# CANOPi_Topboard_USB3.net
KiCad netlist of a schematic drawn in Altium Designer
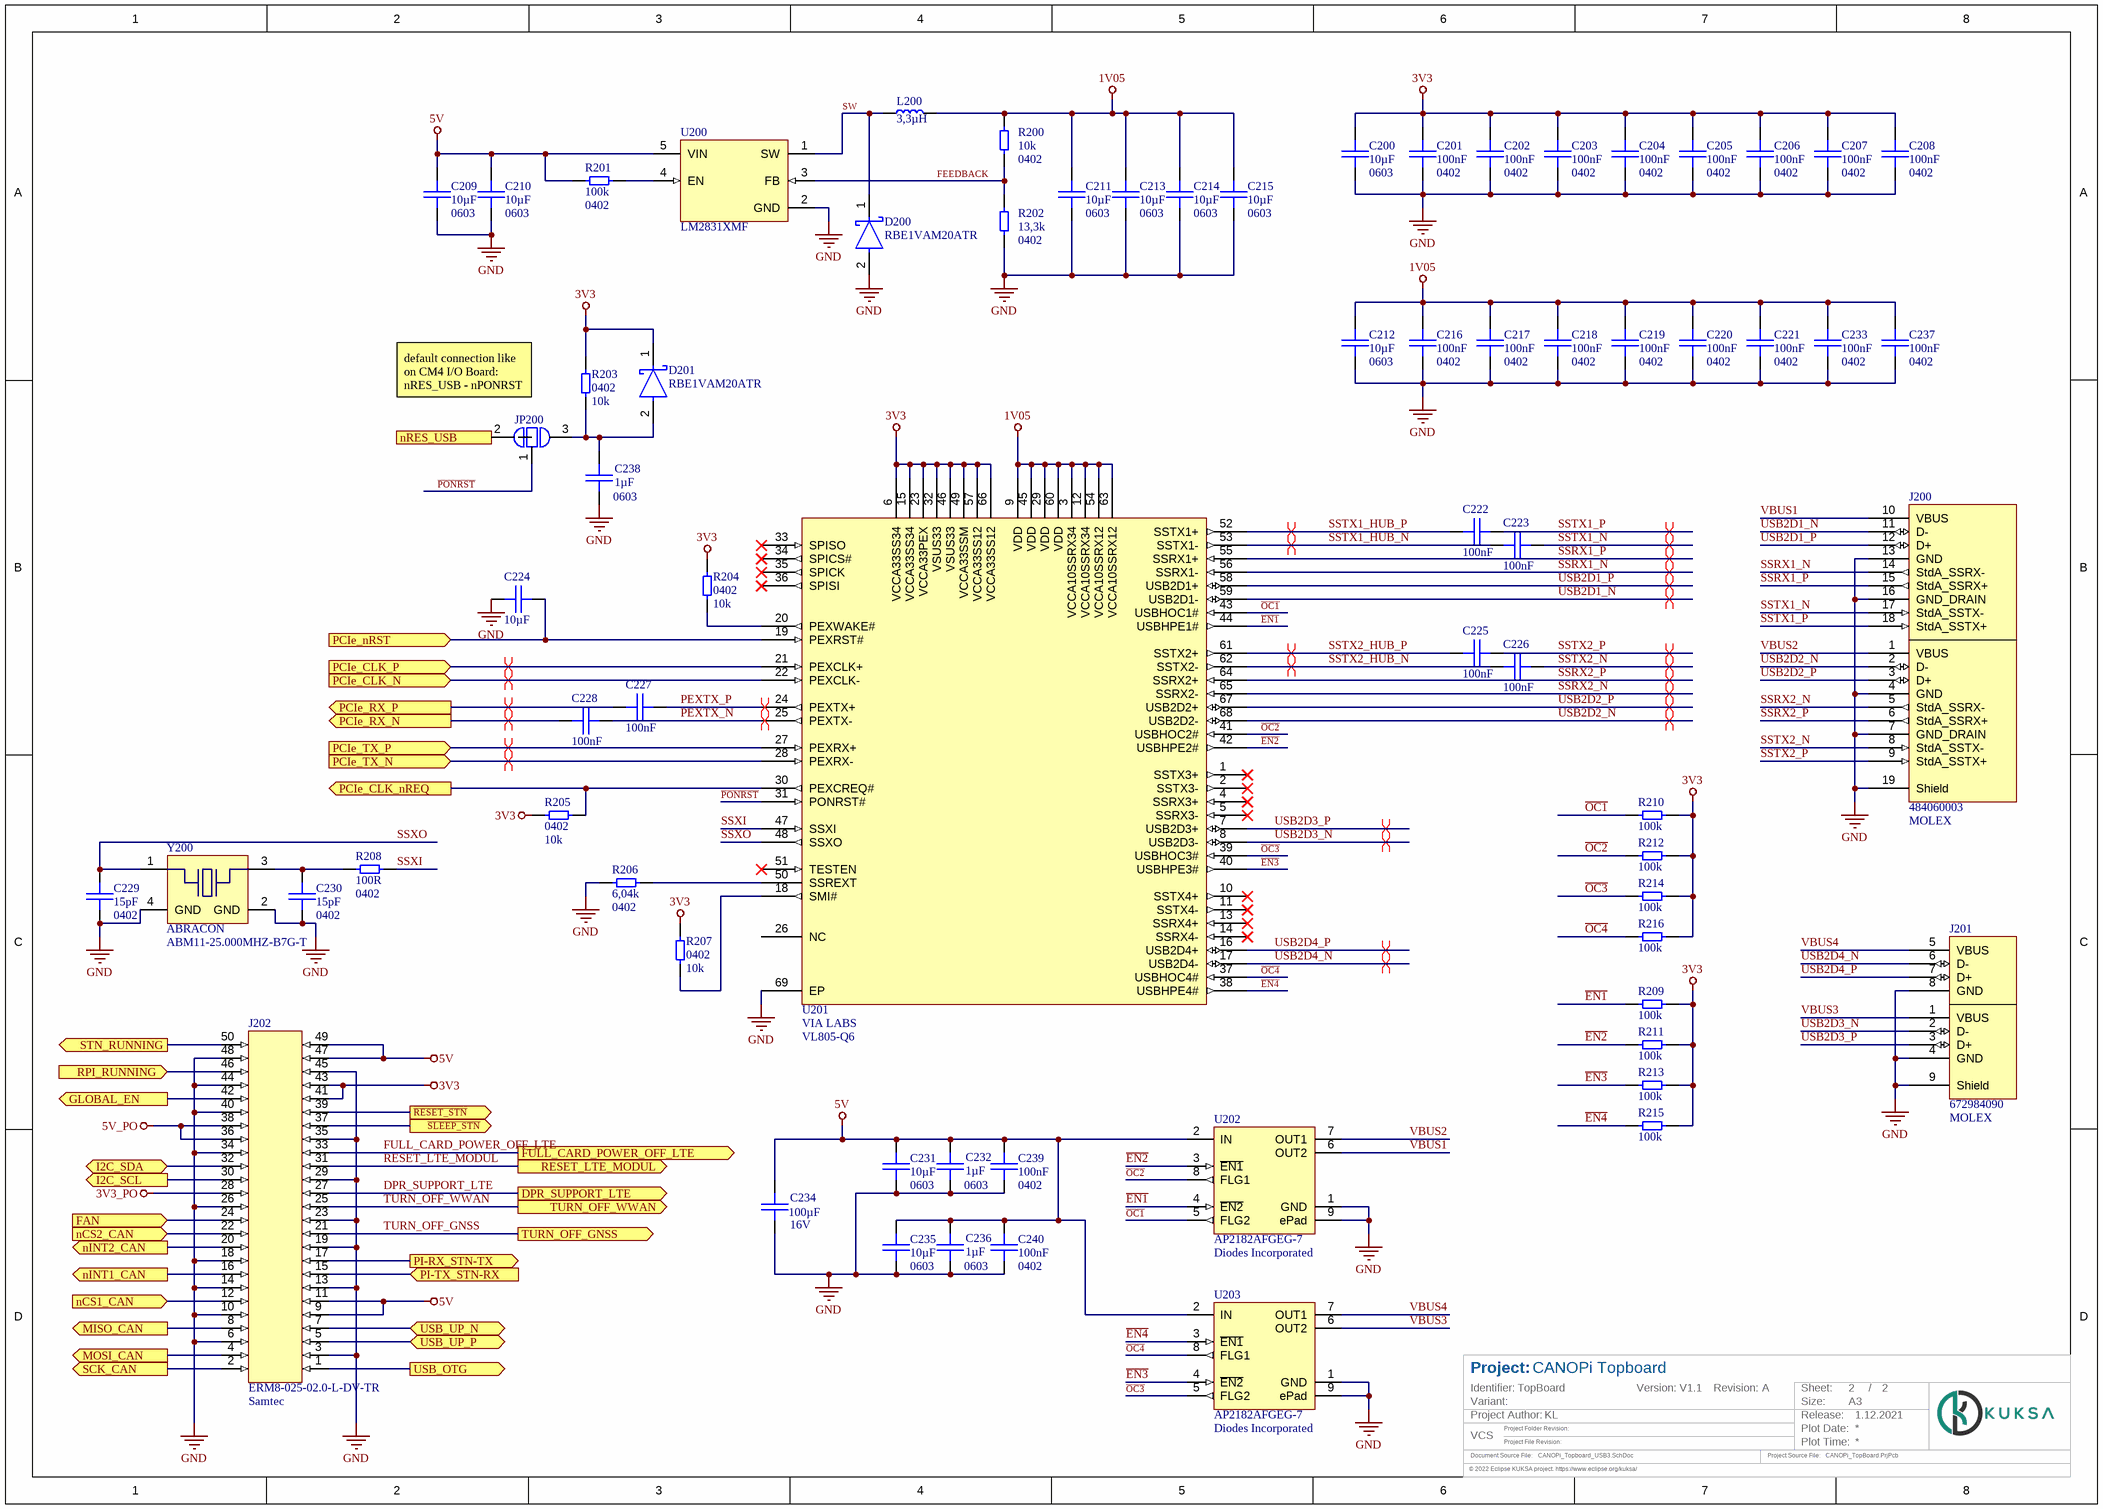
[diagram p0: CANOPi_Topboard_USB3.SchDoc]

(export (version "E")
  (design (tool "Eeschema 10.0.6"))
  (components
    (comp (ref "C200")
      (value "CAP 0603 10µF -20% +20% 6.3V X5R")
      (footprint "CAP 0603 [1608 Metric] X080 N")
      (description "SMT 10µF ±20% 6,3 V Keramikkondensatoren X5R")
      (fields
        (field (name "MANUFACTURER PART NUMBER") "GRM188R60J106ME84")
        (field (name "CAPACITANCE") "10µF")
        (field (name "MANUFACTURER") "MURATA")
        (field (name "CASE") "0603")
      )
      (libsource (lib "ShareLib") (part "Capacitor non-polarized - Standard Schematic"))
    )
    (comp (ref "C201")
      (value "CAP 0402 100n -10% +10% 6.3V X7R")
      (footprint "CAP 0402 [1005 Metric] X050 N")
      (description "SMD/SMT 0402 6.3V -10% +10% X7R - Multilayer Ceramic Capacitors MLCC")
      (fields
        (field (name "MANUFACTURER") "MURATA")
        (field (name "CAPACITANCE") "100nF")
        (field (name "MANUFACTURER PART NUMBER") "GRM155R70J104KA01#")
        (field (name "CASE") "0402")
      )
      (libsource (lib "ShareLib") (part "Capacitor non-polarized - Standard Schematic"))
    )
    (comp (ref "C202")
      (value "CAP 0402 100n -10% +10% 6.3V X7R")
      (footprint "CAP 0402 [1005 Metric] X050 N")
      (description "SMD/SMT 0402 6.3V -10% +10% X7R - Multilayer Ceramic Capacitors MLCC")
      (fields
        (field (name "MANUFACTURER") "MURATA")
        (field (name "CAPACITANCE") "100nF")
        (field (name "MANUFACTURER PART NUMBER") "GRM155R70J104KA01#")
        (field (name "CASE") "0402")
      )
      (libsource (lib "ShareLib") (part "Capacitor non-polarized - Standard Schematic"))
    )
    (comp (ref "C203")
      (value "CAP 0402 100n -10% +10% 6.3V X7R")
      (footprint "CAP 0402 [1005 Metric] X050 N")
      (description "SMD/SMT 0402 6.3V -10% +10% X7R - Multilayer Ceramic Capacitors MLCC")
      (fields
        (field (name "MANUFACTURER") "MURATA")
        (field (name "CAPACITANCE") "100nF")
        (field (name "MANUFACTURER PART NUMBER") "GRM155R70J104KA01#")
        (field (name "CASE") "0402")
      )
      (libsource (lib "ShareLib") (part "Capacitor non-polarized - Standard Schematic"))
    )
    (comp (ref "C204")
      (value "CAP 0402 100n -10% +10% 6.3V X7R")
      (footprint "CAP 0402 [1005 Metric] X050 N")
      (description "SMD/SMT 0402 6.3V -10% +10% X7R - Multilayer Ceramic Capacitors MLCC")
      (fields
        (field (name "MANUFACTURER") "MURATA")
        (field (name "CAPACITANCE") "100nF")
        (field (name "MANUFACTURER PART NUMBER") "GRM155R70J104KA01#")
        (field (name "CASE") "0402")
      )
      (libsource (lib "ShareLib") (part "Capacitor non-polarized - Standard Schematic"))
    )
    (comp (ref "C205")
      (value "CAP 0402 100n -10% +10% 6.3V X7R")
      (footprint "CAP 0402 [1005 Metric] X050 N")
      (description "SMD/SMT 0402 6.3V -10% +10% X7R - Multilayer Ceramic Capacitors MLCC")
      (fields
        (field (name "MANUFACTURER") "MURATA")
        (field (name "CAPACITANCE") "100nF")
        (field (name "MANUFACTURER PART NUMBER") "GRM155R70J104KA01#")
        (field (name "CASE") "0402")
      )
      (libsource (lib "ShareLib") (part "Capacitor non-polarized - Standard Schematic"))
    )
    (comp (ref "C206")
      (value "CAP 0402 100n -10% +10% 6.3V X7R")
      (footprint "CAP 0402 [1005 Metric] X050 N")
      (description "SMD/SMT 0402 6.3V -10% +10% X7R - Multilayer Ceramic Capacitors MLCC")
      (fields
        (field (name "MANUFACTURER") "MURATA")
        (field (name "CAPACITANCE") "100nF")
        (field (name "MANUFACTURER PART NUMBER") "GRM155R70J104KA01#")
        (field (name "CASE") "0402")
      )
      (libsource (lib "ShareLib") (part "Capacitor non-polarized - Standard Schematic"))
    )
    (comp (ref "C207")
      (value "CAP 0402 100n -10% +10% 6.3V X7R")
      (footprint "CAP 0402 [1005 Metric] X050 N")
      (description "SMD/SMT 0402 6.3V -10% +10% X7R - Multilayer Ceramic Capacitors MLCC")
      (fields
        (field (name "MANUFACTURER") "MURATA")
        (field (name "CAPACITANCE") "100nF")
        (field (name "MANUFACTURER PART NUMBER") "GRM155R70J104KA01#")
        (field (name "CASE") "0402")
      )
      (libsource (lib "ShareLib") (part "Capacitor non-polarized - Standard Schematic"))
    )
    (comp (ref "C208")
      (value "CAP 0402 100n -10% +10% 6.3V X7R")
      (footprint "CAP 0402 [1005 Metric] X050 N")
      (description "SMD/SMT 0402 6.3V -10% +10% X7R - Multilayer Ceramic Capacitors MLCC")
      (fields
        (field (name "MANUFACTURER") "MURATA")
        (field (name "CAPACITANCE") "100nF")
        (field (name "MANUFACTURER PART NUMBER") "GRM155R70J104KA01#")
        (field (name "CASE") "0402")
      )
      (libsource (lib "ShareLib") (part "Capacitor non-polarized - Standard Schematic"))
    )
    (comp (ref "C209")
      (value "CAP 0603 10µF -20% +20% 6.3V X5R")
      (footprint "CAP 0603 [1608 Metric] X080 N")
      (description "SMT 10µF ±20% 6,3 V Keramikkondensatoren X5R")
      (fields
        (field (name "MANUFACTURER PART NUMBER") "GRM188R60J106ME84")
        (field (name "CAPACITANCE") "10µF")
        (field (name "MANUFACTURER") "MURATA")
        (field (name "CASE") "0603")
      )
      (libsource (lib "ShareLib") (part "Capacitor non-polarized - Standard Schematic"))
    )
    (comp (ref "C210")
      (value "CAP 0603 10µF -20% +20% 6.3V X5R")
      (footprint "CAP 0603 [1608 Metric] X080 N")
      (description "SMT 10µF ±20% 6,3 V Keramikkondensatoren X5R")
      (fields
        (field (name "MANUFACTURER PART NUMBER") "GRM188R60J106ME84")
        (field (name "CAPACITANCE") "10µF")
        (field (name "MANUFACTURER") "MURATA")
        (field (name "CASE") "0603")
      )
      (libsource (lib "ShareLib") (part "Capacitor non-polarized - Standard Schematic"))
    )
    (comp (ref "C211")
      (value "CAP 0603 10µF -20% +20% 6.3V X5R")
      (footprint "CAP 0603 [1608 Metric] X080 N")
      (description "SMT 10µF ±20% 6,3 V Keramikkondensatoren X5R")
      (fields
        (field (name "MANUFACTURER PART NUMBER") "GRM188R60J106ME84")
        (field (name "CAPACITANCE") "10µF")
        (field (name "MANUFACTURER") "MURATA")
        (field (name "CASE") "0603")
      )
      (libsource (lib "ShareLib") (part "Capacitor non-polarized - Standard Schematic"))
    )
    (comp (ref "C212")
      (value "CAP 0603 10µF -20% +20% 6.3V X5R")
      (footprint "CAP 0603 [1608 Metric] X080 N")
      (description "SMT 10µF ±20% 6,3 V Keramikkondensatoren X5R")
      (fields
        (field (name "MANUFACTURER PART NUMBER") "GRM188R60J106ME84")
        (field (name "CAPACITANCE") "10µF")
        (field (name "MANUFACTURER") "MURATA")
        (field (name "CASE") "0603")
      )
      (libsource (lib "ShareLib") (part "Capacitor non-polarized - Standard Schematic"))
    )
    (comp (ref "C213")
      (value "CAP 0603 10µF -20% +20% 6.3V X5R")
      (footprint "CAP 0603 [1608 Metric] X080 N")
      (description "SMT 10µF ±20% 6,3 V Keramikkondensatoren X5R")
      (fields
        (field (name "MANUFACTURER PART NUMBER") "GRM188R60J106ME84")
        (field (name "CAPACITANCE") "10µF")
        (field (name "MANUFACTURER") "MURATA")
        (field (name "CASE") "0603")
      )
      (libsource (lib "ShareLib") (part "Capacitor non-polarized - Standard Schematic"))
    )
    (comp (ref "C214")
      (value "CAP 0603 10µF -20% +20% 6.3V X5R")
      (footprint "CAP 0603 [1608 Metric] X080 N")
      (description "SMT 10µF ±20% 6,3 V Keramikkondensatoren X5R")
      (fields
        (field (name "MANUFACTURER PART NUMBER") "GRM188R60J106ME84")
        (field (name "CAPACITANCE") "10µF")
        (field (name "MANUFACTURER") "MURATA")
        (field (name "CASE") "0603")
      )
      (libsource (lib "ShareLib") (part "Capacitor non-polarized - Standard Schematic"))
    )
    (comp (ref "C215")
      (value "CAP 0603 10µF -20% +20% 6.3V X5R")
      (footprint "CAP 0603 [1608 Metric] X080 N")
      (description "SMT 10µF ±20% 6,3 V Keramikkondensatoren X5R")
      (fields
        (field (name "MANUFACTURER PART NUMBER") "GRM188R60J106ME84")
        (field (name "CAPACITANCE") "10µF")
        (field (name "MANUFACTURER") "MURATA")
        (field (name "CASE") "0603")
      )
      (libsource (lib "ShareLib") (part "Capacitor non-polarized - Standard Schematic"))
    )
    (comp (ref "C216")
      (value "CAP 0402 100n -10% +10% 6.3V X7R")
      (footprint "CAP 0402 [1005 Metric] X050 N")
      (description "SMD/SMT 0402 6.3V -10% +10% X7R - Multilayer Ceramic Capacitors MLCC")
      (fields
        (field (name "MANUFACTURER") "MURATA")
        (field (name "CAPACITANCE") "100nF")
        (field (name "MANUFACTURER PART NUMBER") "GRM155R70J104KA01#")
        (field (name "CASE") "0402")
      )
      (libsource (lib "ShareLib") (part "Capacitor non-polarized - Standard Schematic"))
    )
    (comp (ref "C217")
      (value "CAP 0402 100n -10% +10% 6.3V X7R")
      (footprint "CAP 0402 [1005 Metric] X050 N")
      (description "SMD/SMT 0402 6.3V -10% +10% X7R - Multilayer Ceramic Capacitors MLCC")
      (fields
        (field (name "MANUFACTURER") "MURATA")
        (field (name "CAPACITANCE") "100nF")
        (field (name "MANUFACTURER PART NUMBER") "GRM155R70J104KA01#")
        (field (name "CASE") "0402")
      )
      (libsource (lib "ShareLib") (part "Capacitor non-polarized - Standard Schematic"))
    )
    (comp (ref "C218")
      (value "CAP 0402 100n -10% +10% 6.3V X7R")
      (footprint "CAP 0402 [1005 Metric] X050 N")
      (description "SMD/SMT 0402 6.3V -10% +10% X7R - Multilayer Ceramic Capacitors MLCC")
      (fields
        (field (name "MANUFACTURER") "MURATA")
        (field (name "CAPACITANCE") "100nF")
        (field (name "MANUFACTURER PART NUMBER") "GRM155R70J104KA01#")
        (field (name "CASE") "0402")
      )
      (libsource (lib "ShareLib") (part "Capacitor non-polarized - Standard Schematic"))
    )
    (comp (ref "C219")
      (value "CAP 0402 100n -10% +10% 6.3V X7R")
      (footprint "CAP 0402 [1005 Metric] X050 N")
      (description "SMD/SMT 0402 6.3V -10% +10% X7R - Multilayer Ceramic Capacitors MLCC")
      (fields
        (field (name "MANUFACTURER") "MURATA")
        (field (name "CAPACITANCE") "100nF")
        (field (name "MANUFACTURER PART NUMBER") "GRM155R70J104KA01#")
        (field (name "CASE") "0402")
      )
      (libsource (lib "ShareLib") (part "Capacitor non-polarized - Standard Schematic"))
    )
    (comp (ref "C220")
      (value "CAP 0402 100n -10% +10% 6.3V X7R")
      (footprint "CAP 0402 [1005 Metric] X050 N")
      (description "SMD/SMT 0402 6.3V -10% +10% X7R - Multilayer Ceramic Capacitors MLCC")
      (fields
        (field (name "MANUFACTURER") "MURATA")
        (field (name "CAPACITANCE") "100nF")
        (field (name "MANUFACTURER PART NUMBER") "GRM155R70J104KA01#")
        (field (name "CASE") "0402")
      )
      (libsource (lib "ShareLib") (part "Capacitor non-polarized - Standard Schematic"))
    )
    (comp (ref "C221")
      (value "CAP 0402 100n -10% +10% 6.3V X7R")
      (footprint "CAP 0402 [1005 Metric] X050 N")
      (description "SMD/SMT 0402 6.3V -10% +10% X7R - Multilayer Ceramic Capacitors MLCC")
      (fields
        (field (name "MANUFACTURER") "MURATA")
        (field (name "CAPACITANCE") "100nF")
        (field (name "MANUFACTURER PART NUMBER") "GRM155R70J104KA01#")
        (field (name "CASE") "0402")
      )
      (libsource (lib "ShareLib") (part "Capacitor non-polarized - Standard Schematic"))
    )
    (comp (ref "C222")
      (value "CAP 0402 100n -10% +10% 6.3V X7R")
      (footprint "CAP 0402 [1005 Metric] X050 N")
      (description "SMD/SMT 0402 6.3V -10% +10% X7R - Multilayer Ceramic Capacitors MLCC")
      (fields
        (field (name "MANUFACTURER") "MURATA")
        (field (name "CAPACITANCE") "100nF")
        (field (name "MANUFACTURER PART NUMBER") "GRM155R70J104KA01#")
      )
      (libsource (lib "ShareLib") (part "Capacitor non-polarized - Standard Schematic"))
    )
    (comp (ref "C223")
      (value "CAP 0402 100n -10% +10% 6.3V X7R")
      (footprint "CAP 0402 [1005 Metric] X050 N")
      (description "SMD/SMT 0402 6.3V -10% +10% X7R - Multilayer Ceramic Capacitors MLCC")
      (fields
        (field (name "MANUFACTURER") "MURATA")
        (field (name "CAPACITANCE") "100nF")
        (field (name "MANUFACTURER PART NUMBER") "GRM155R70J104KA01#")
      )
      (libsource (lib "ShareLib") (part "Capacitor non-polarized - Standard Schematic"))
    )
    (comp (ref "C224")
      (value "CAP 0603 10µF -20% +20% 6.3V X5R")
      (footprint "CAP 0603 [1608 Metric] X080 N")
      (description "SMT 10µF ±20% 6,3 V Keramikkondensatoren X5R")
      (fields
        (field (name "MANUFACTURER PART NUMBER") "GRM188R60J106ME84")
        (field (name "CAPACITANCE") "10µF")
        (field (name "MANUFACTURER") "MURATA")
      )
      (libsource (lib "ShareLib") (part "Capacitor non-polarized - Standard Schematic"))
    )
    (comp (ref "C225")
      (value "CAP 0402 100n -10% +10% 6.3V X7R")
      (footprint "CAP 0402 [1005 Metric] X050 N")
      (description "SMD/SMT 0402 6.3V -10% +10% X7R - Multilayer Ceramic Capacitors MLCC")
      (fields
        (field (name "MANUFACTURER") "MURATA")
        (field (name "CAPACITANCE") "100nF")
        (field (name "MANUFACTURER PART NUMBER") "GRM155R70J104KA01#")
      )
      (libsource (lib "ShareLib") (part "Capacitor non-polarized - Standard Schematic"))
    )
    (comp (ref "C226")
      (value "CAP 0402 100n -10% +10% 6.3V X7R")
      (footprint "CAP 0402 [1005 Metric] X050 N")
      (description "SMD/SMT 0402 6.3V -10% +10% X7R - Multilayer Ceramic Capacitors MLCC")
      (fields
        (field (name "MANUFACTURER") "MURATA")
        (field (name "CAPACITANCE") "100nF")
        (field (name "MANUFACTURER PART NUMBER") "GRM155R70J104KA01#")
      )
      (libsource (lib "ShareLib") (part "Capacitor non-polarized - Standard Schematic"))
    )
    (comp (ref "C227")
      (value "CAP 0402 100n -10% +10% 6.3V X7R")
      (footprint "CAP 0402 [1005 Metric] X050 N")
      (description "SMD/SMT 0402 6.3V -10% +10% X7R - Multilayer Ceramic Capacitors MLCC")
      (fields
        (field (name "MANUFACTURER") "MURATA")
        (field (name "CAPACITANCE") "100nF")
        (field (name "MANUFACTURER PART NUMBER") "GRM155R70J104KA01#")
      )
      (libsource (lib "ShareLib") (part "Capacitor non-polarized - Standard Schematic"))
    )
    (comp (ref "C228")
      (value "CAP 0402 100n -10% +10% 6.3V X7R")
      (footprint "CAP 0402 [1005 Metric] X050 N")
      (description "SMD/SMT 0402 6.3V -10% +10% X7R - Multilayer Ceramic Capacitors MLCC")
      (fields
        (field (name "MANUFACTURER") "MURATA")
        (field (name "CAPACITANCE") "100nF")
        (field (name "MANUFACTURER PART NUMBER") "GRM155R70J104KA01#")
      )
      (libsource (lib "ShareLib") (part "Capacitor non-polarized - Standard Schematic"))
    )
    (comp (ref "C229")
      (value "CAP 0402 15p -2% +2% 25V C0G")
      (footprint "CAP 0402 [1005 Metric] X050 N")
      (description "SMD/SMT 0402 25V -2% +2% C0G - Multilayer Ceramic Capacitors MLCC")
      (fields
        (field (name "MANUFACTURER") "MURATA")
        (field (name "MANUFACTURER PART NUMBER") "GRM1555C1E150GA01#")
        (field (name "CASE") "0402")
        (field (name "CAPACITANCE") "15pF")
      )
      (libsource (lib "ShareLib") (part "Capacitor non-polarized - Standard Schematic"))
    )
    (comp (ref "C230")
      (value "CAP 0402 15p -2% +2% 25V C0G")
      (footprint "CAP 0402 [1005 Metric] X050 N")
      (description "SMD/SMT 0402 25V -2% +2% C0G - Multilayer Ceramic Capacitors MLCC")
      (fields
        (field (name "MANUFACTURER") "MURATA")
        (field (name "MANUFACTURER PART NUMBER") "GRM1555C1E150GA01#")
        (field (name "CASE") "0402")
        (field (name "CAPACITANCE") "15pF")
      )
      (libsource (lib "ShareLib") (part "Capacitor non-polarized - Standard Schematic"))
    )
    (comp (ref "C231")
      (value "CAP 0603 10µF -20% +20% 6.3V X5R")
      (footprint "CAP 0603 [1608 Metric] X080 N")
      (description "SMT 10µF ±20% 6,3 V Keramikkondensatoren X5R")
      (fields
        (field (name "MANUFACTURER PART NUMBER") "GRM188R60J106ME84")
        (field (name "CAPACITANCE") "10µF")
        (field (name "MANUFACTURER") "MURATA")
        (field (name "CASE") "0603")
      )
      (libsource (lib "ShareLib") (part "Capacitor non-polarized - Standard Schematic"))
    )
    (comp (ref "C232")
      (value "CAP 0603 1u -10% +10% 10V X7R")
      (footprint "CAP 0603 [1608 Metric] X080 N")
      (description "SMD/SMT 0603 10V -10% +10% X7R - Multilayer Ceramic Capacitors MLCC")
      (fields
        (field (name "CAPACITANCE") "1µF")
        (field (name "MANUFACTURER PART NUMBER") "GRM188R71A105KA61#")
        (field (name "MANUFACTURER") "MURATA")
        (field (name "CASE") "0603")
      )
      (libsource (lib "ShareLib") (part "Capacitor non-polarized - Standard Schematic"))
    )
    (comp (ref "C233")
      (value "CAP 0402 100n -10% +10% 6.3V X7R")
      (footprint "CAP 0402 [1005 Metric] X050 N")
      (description "SMD/SMT 0402 6.3V -10% +10% X7R - Multilayer Ceramic Capacitors MLCC")
      (fields
        (field (name "MANUFACTURER") "MURATA")
        (field (name "CAPACITANCE") "100nF")
        (field (name "MANUFACTURER PART NUMBER") "GRM155R70J104KA01#")
        (field (name "CASE") "0402")
      )
      (libsource (lib "ShareLib") (part "Capacitor non-polarized - Standard Schematic"))
    )
    (comp (ref "C234")
      (value "CAP 1210 100µF +/-20% 16V X5R")
      (footprint "CAP 1210 [3225 Metric] X250 N")
      (description "100µF ±20% 16V Ceramic Capacitor X5R 1210 (3225 Metric)")
      (fields
        (field (name "MANUFACTURER PART NUMBER") "EMK325ABJ107MM-T")
        (field (name "VOLTAGE RATING") "16V")
        (field (name "MANUFACTURER") "TAIYO YUDEN")
        (field (name "CAPACITANCE") "100µF")
      )
      (libsource (lib "ShareLib") (part "Capacitor non-polarized - Standard Schematic"))
    )
    (comp (ref "C235")
      (value "CAP 0603 10µF -20% +20% 6.3V X5R")
      (footprint "CAP 0603 [1608 Metric] X080 N")
      (description "SMT 10µF ±20% 6,3 V Keramikkondensatoren X5R")
      (fields
        (field (name "MANUFACTURER PART NUMBER") "GRM188R60J106ME84")
        (field (name "CAPACITANCE") "10µF")
        (field (name "MANUFACTURER") "MURATA")
        (field (name "CASE") "0603")
      )
      (libsource (lib "ShareLib") (part "Capacitor non-polarized - Standard Schematic"))
    )
    (comp (ref "C236")
      (value "CAP 0603 1u -10% +10% 10V X7R")
      (footprint "CAP 0603 [1608 Metric] X080 N")
      (description "SMD/SMT 0603 10V -10% +10% X7R - Multilayer Ceramic Capacitors MLCC")
      (fields
        (field (name "CAPACITANCE") "1µF")
        (field (name "MANUFACTURER PART NUMBER") "GRM188R71A105KA61#")
        (field (name "MANUFACTURER") "MURATA")
        (field (name "CASE") "0603")
      )
      (libsource (lib "ShareLib") (part "Capacitor non-polarized - Standard Schematic"))
    )
    (comp (ref "C237")
      (value "CAP 0402 100n -10% +10% 6.3V X7R")
      (footprint "CAP 0402 [1005 Metric] X050 N")
      (description "SMD/SMT 0402 6.3V -10% +10% X7R - Multilayer Ceramic Capacitors MLCC")
      (fields
        (field (name "MANUFACTURER") "MURATA")
        (field (name "CAPACITANCE") "100nF")
        (field (name "MANUFACTURER PART NUMBER") "GRM155R70J104KA01#")
        (field (name "CASE") "0402")
      )
      (libsource (lib "ShareLib") (part "Capacitor non-polarized - Standard Schematic"))
    )
    (comp (ref "C238")
      (value "CAP 0603 1u -10% +10% 10V X7R")
      (footprint "CAP 0603 [1608 Metric] X080 N")
      (description "SMD/SMT 0603 10V -10% +10% X7R - Multilayer Ceramic Capacitors MLCC")
      (fields
        (field (name "CAPACITANCE") "1µF")
        (field (name "MANUFACTURER PART NUMBER") "GRM188R71A105KA61#")
        (field (name "MANUFACTURER") "MURATA")
        (field (name "CASE") "0603")
      )
      (libsource (lib "ShareLib") (part "Capacitor non-polarized - Standard Schematic"))
    )
    (comp (ref "C239")
      (value "CAP 0402 100n -10% +10% 6.3V X7R")
      (footprint "CAP 0402 [1005 Metric] X050 N")
      (description "SMD/SMT 0402 6.3V -10% +10% X7R - Multilayer Ceramic Capacitors MLCC")
      (fields
        (field (name "MANUFACTURER") "MURATA")
        (field (name "CAPACITANCE") "100nF")
        (field (name "MANUFACTURER PART NUMBER") "GRM155R70J104KA01#")
        (field (name "CASE") "0402")
      )
      (libsource (lib "ShareLib") (part "Capacitor non-polarized - Standard Schematic"))
    )
    (comp (ref "C240")
      (value "CAP 0402 100n -10% +10% 6.3V X7R")
      (footprint "CAP 0402 [1005 Metric] X050 N")
      (description "SMD/SMT 0402 6.3V -10% +10% X7R - Multilayer Ceramic Capacitors MLCC")
      (fields
        (field (name "MANUFACTURER") "MURATA")
        (field (name "CAPACITANCE") "100nF")
        (field (name "MANUFACTURER PART NUMBER") "GRM155R70J104KA01#")
        (field (name "CASE") "0402")
      )
      (libsource (lib "ShareLib") (part "Capacitor non-polarized - Standard Schematic"))
    )
    (comp (ref "D200")
      (value "RBE1VAM20ATR")
      (footprint "FP-TUMD2M-MFG")
      (description "DIODE SCHOTTKY 20V 1A TUMD2M")
      (fields
        (field (name "OCTOPART") "https://octopart.com/rbe1vam20atr-rohm-50418626")
        (field (name "MANUFACTURER") "Rohm")
      )
      (libsource (lib "Altium Content Vault") (part "c1678fac7984e62e0809fbf79c06691"))
    )
    (comp (ref "D201")
      (value "RBE1VAM20ATR")
      (footprint "FP-TUMD2M-MFG")
      (description "DIODE SCHOTTKY 20V 1A TUMD2M")
      (fields
        (field (name "OCTOPART") "https://octopart.com/rbe1vam20atr-rohm-50418626")
        (field (name "MANUFACTURER") "Rohm")
      )
      (libsource (lib "Altium Content Vault") (part "c1678fac7984e62e0809fbf79c06691"))
    )
    (comp (ref "J200")
      (value "MOLEX - 484060003")
      (footprint "MOLEX - 484060003")
      (fields (field (name "MANUFACTURER PART NUMBER") "484060003") (field (name "MANUFACTURER") "MOLEX"))
      (libsource (lib "ShareLib") (part "MOLEX - 484060003"))
    )
    (comp (ref "J201")
      (value "MOLEX - 672984090")
      (footprint "MOLEX - 672984090")
      (fields (field (name "MANUFACTURER PART NUMBER") "672984090") (field (name "MANUFACTURER") "MOLEX"))
      (libsource (lib "ShareLib") (part "MOLEX - 672984090"))
    )
    (comp (ref "J202")
      (value "SAMTEC - ERM8-025-02.0-L-DV-TR")
      (footprint "SAMTEC - ERM8-025-02.0-S-DV-TR-Footprint-1")
      (description "50 Poliger Steckverbinder Steckleiste, Mittenstreifenkontakte Oberflächenmontage Gold")
      (fields
        (field (name "MANUFACTURER PART NUMBER") "ERM8-025-02.0-L-DV-TR")
        (field (name "MANUFACTURER") "Samtec")
      )
      (libsource (lib "ShareLib") (part "SAMTEC - ERM8-025-02.0-S-DV-TR"))
    )
    (comp (ref "JP200")
      (value "Solder Jumper Triple 0402 with Assembly between 1 and 2")
      (footprint "Solder Jumper Triple 0402 with Assembly between 1 and 2")
      (fields
        (field (name "MANUFACTURER") "YAGEO")
        (field (name "MANUFACTURER PART NUMBER") "RC0402JR-070RL")
      )
      (libsource (lib "ShareLib") (part "Solder Jumper tripple with Assembly between 1 and 2"))
    )
    (comp (ref "L200")
      (value "VISHAY - IFSC1515AHER3R3M01")
      (footprint "IFSC-1515AH")
      (description "Low Profile, High Current Inductor")
      (fields
        (field (name "MANUFACTURER PART NUMBER") "IFSC1515AHER3R3M01")
        (field (name "MANUFACTURER") "VISHAY")
        (field (name "INDUCTANCE") "3,3µH")
      )
      (libsource (lib "ShareLib") (part "Standard Schematic - Inductor Universal"))
    )
    (comp (ref "R200")
      (value "RES 0402 10K 1% 0W0625")
      (footprint "RES 0402 [1005 Metric]_N")
      (description "RC0402 series chip resistor with lead-free terminations made by thick film process")
      (fields
        (field (name "MANUFACTURER PART NUMBER") "RC0402FR-0710KL")
        (field (name "CASE") "0402")
        (field (name "MANUFACTURER") "YAGEO")
        (field (name "RESISTANCE") "10k")
      )
      (libsource (lib "ShareLib") (part "Standard Schematic - Resistor Universal"))
    )
    (comp (ref "R201")
      (value "RES 0402 100K 1% 0W0625")
      (footprint "RES 0402 [1005 Metric]_N")
      (description "RC0402 series chip resistor with lead-free terminations made by thick film process")
      (fields
        (field (name "RESISTANCE") "100k")
        (field (name "MANUFACTURER PART NUMBER") "RC0402FR-07100KL")
        (field (name "CASE") "0402")
        (field (name "MANUFACTURER") "YAGEO")
      )
      (libsource (lib "ShareLib") (part "Standard Schematic - Resistor Universal"))
    )
    (comp (ref "R202")
      (value "RES 0402 13K3 1% 0W0625")
      (footprint "RES 0402 [1005 Metric]_N")
      (description "RC0402 series chip resistor with lead-free terminations made by thick film process")
      (fields
        (field (name "MANUFACTURER") "YAGEO")
        (field (name "RESISTANCE") "13,3k")
        (field (name "CASE") "0402")
        (field (name "MANUFACTURER PART NUMBER") "RC0402FR-0713K3L")
      )
      (libsource (lib "ShareLib") (part "Standard Schematic - Resistor Universal"))
    )
    (comp (ref "R203")
      (value "RES 0402 10K 1% 0W0625")
      (footprint "RES 0402 [1005 Metric]_N")
      (description "RC0402 series chip resistor with lead-free terminations made by thick film process")
      (fields
        (field (name "MANUFACTURER PART NUMBER") "RC0402FR-0710KL")
        (field (name "CASE") "0402")
        (field (name "MANUFACTURER") "YAGEO")
        (field (name "RESISTANCE") "10k")
      )
      (libsource (lib "ShareLib") (part "Standard Schematic - Resistor Universal"))
    )
    (comp (ref "R204")
      (value "RES 0402 10K 1% 0W0625")
      (footprint "RES 0402 [1005 Metric]_N")
      (description "RC0402 series chip resistor with lead-free terminations made by thick film process")
      (fields
        (field (name "MANUFACTURER PART NUMBER") "RC0402FR-0710KL")
        (field (name "CASE") "0402")
        (field (name "MANUFACTURER") "YAGEO")
        (field (name "RESISTANCE") "10k")
      )
      (libsource (lib "ShareLib") (part "Standard Schematic - Resistor Universal"))
    )
    (comp (ref "R205")
      (value "RES 0402 10K 1% 0W0625")
      (footprint "RES 0402 [1005 Metric]_N")
      (description "RC0402 series chip resistor with lead-free terminations made by thick film process")
      (fields
        (field (name "MANUFACTURER PART NUMBER") "RC0402FR-0710KL")
        (field (name "CASE") "0402")
        (field (name "MANUFACTURER") "YAGEO")
        (field (name "RESISTANCE") "10k")
      )
      (libsource (lib "ShareLib") (part "Standard Schematic - Resistor Universal"))
    )
    (comp (ref "R206")
      (value "RES 0402 6K04 1% 0W0625")
      (footprint "RES 0402 [1005 Metric]_N")
      (description "RC0402 series chip resistor with lead-free terminations made by thick film process")
      (fields
        (field (name "RESISTANCE") "6,04k")
        (field (name "MANUFACTURER") "YAGEO")
        (field (name "MANUFACTURER PART NUMBER") "RC0402FR-076K04L")
        (field (name "CASE") "0402")
      )
      (libsource (lib "ShareLib") (part "Standard Schematic - Resistor Universal"))
    )
    (comp (ref "R207")
      (value "RES 0402 10K 1% 0W0625")
      (footprint "RES 0402 [1005 Metric]_N")
      (description "RC0402 series chip resistor with lead-free terminations made by thick film process")
      (fields
        (field (name "MANUFACTURER PART NUMBER") "RC0402FR-0710KL")
        (field (name "CASE") "0402")
        (field (name "MANUFACTURER") "YAGEO")
        (field (name "RESISTANCE") "10k")
      )
      (libsource (lib "ShareLib") (part "Standard Schematic - Resistor Universal"))
    )
    (comp (ref "R208")
      (value "RES 0402 100R 1% 63mW")
      (footprint "RES 0402 [1005 Metric]_N")
      (description "RC0402 series chip resistor with lead-free terminations made by thick film process")
      (fields
        (field (name "RESISTANCE") "100R")
        (field (name "CASE") "0402")
        (field (name "MANUFACTURER") "ROHM")
        (field (name "MANUFACTURER PART NUMBER") "MCR01MZPF100")
      )
      (libsource (lib "ShareLib") (part "Standard Schematic - Resistor Universal"))
    )
    (comp (ref "R209")
      (value "RES 0402 100K 1% 0W0625")
      (footprint "RES 0402 [1005 Metric]_N")
      (description "RC0402 series chip resistor with lead-free terminations made by thick film process")
      (fields
        (field (name "RESISTANCE") "100k")
        (field (name "MANUFACTURER PART NUMBER") "RC0402FR-07100KL")
        (field (name "MANUFACTURER") "YAGEO")
      )
      (libsource (lib "ShareLib") (part "Standard Schematic - Resistor Universal"))
    )
    (comp (ref "R210")
      (value "RES 0402 100K 1% 0W0625")
      (footprint "RES 0402 [1005 Metric]_N")
      (description "RC0402 series chip resistor with lead-free terminations made by thick film process")
      (fields
        (field (name "RESISTANCE") "100k")
        (field (name "MANUFACTURER PART NUMBER") "RC0402FR-07100KL")
        (field (name "MANUFACTURER") "YAGEO")
      )
      (libsource (lib "ShareLib") (part "Standard Schematic - Resistor Universal"))
    )
    (comp (ref "R211")
      (value "RES 0402 100K 1% 0W0625")
      (footprint "RES 0402 [1005 Metric]_N")
      (description "RC0402 series chip resistor with lead-free terminations made by thick film process")
      (fields
        (field (name "RESISTANCE") "100k")
        (field (name "MANUFACTURER PART NUMBER") "RC0402FR-07100KL")
        (field (name "MANUFACTURER") "YAGEO")
      )
      (libsource (lib "ShareLib") (part "Standard Schematic - Resistor Universal"))
    )
    (comp (ref "R212")
      (value "RES 0402 100K 1% 0W0625")
      (footprint "RES 0402 [1005 Metric]_N")
      (description "RC0402 series chip resistor with lead-free terminations made by thick film process")
      (fields
        (field (name "RESISTANCE") "100k")
        (field (name "MANUFACTURER PART NUMBER") "RC0402FR-07100KL")
        (field (name "MANUFACTURER") "YAGEO")
      )
      (libsource (lib "ShareLib") (part "Standard Schematic - Resistor Universal"))
    )
    (comp (ref "R213")
      (value "RES 0402 100K 1% 0W0625")
      (footprint "RES 0402 [1005 Metric]_N")
      (description "RC0402 series chip resistor with lead-free terminations made by thick film process")
      (fields
        (field (name "RESISTANCE") "100k")
        (field (name "MANUFACTURER PART NUMBER") "RC0402FR-07100KL")
        (field (name "MANUFACTURER") "YAGEO")
      )
      (libsource (lib "ShareLib") (part "Standard Schematic - Resistor Universal"))
    )
    (comp (ref "R214")
      (value "RES 0402 100K 1% 0W0625")
      (footprint "RES 0402 [1005 Metric]_N")
      (description "RC0402 series chip resistor with lead-free terminations made by thick film process")
      (fields
        (field (name "RESISTANCE") "100k")
        (field (name "MANUFACTURER PART NUMBER") "RC0402FR-07100KL")
        (field (name "MANUFACTURER") "YAGEO")
      )
      (libsource (lib "ShareLib") (part "Standard Schematic - Resistor Universal"))
    )
    (comp (ref "R215")
      (value "RES 0402 100K 1% 0W0625")
      (footprint "RES 0402 [1005 Metric]_N")
      (description "RC0402 series chip resistor with lead-free terminations made by thick film process")
      (fields
        (field (name "RESISTANCE") "100k")
        (field (name "MANUFACTURER PART NUMBER") "RC0402FR-07100KL")
        (field (name "MANUFACTURER") "YAGEO")
      )
      (libsource (lib "ShareLib") (part "Standard Schematic - Resistor Universal"))
    )
    (comp (ref "R216")
      (value "RES 0402 100K 1% 0W0625")
      (footprint "RES 0402 [1005 Metric]_N")
      (description "RC0402 series chip resistor with lead-free terminations made by thick film process")
      (fields
        (field (name "RESISTANCE") "100k")
        (field (name "MANUFACTURER PART NUMBER") "RC0402FR-07100KL")
        (field (name "MANUFACTURER") "YAGEO")
      )
      (libsource (lib "ShareLib") (part "Standard Schematic - Resistor Universal"))
    )
    (comp (ref "U200")
      (value "LM2831XMF")
      (footprint "MF05A_N")
      (description "High Frequency 1.5A Load - Step-Down DC-DC Regulator, 5-pin SOT-23")
      (fields (field (name "MANUFACTURER") "National Semiconductor"))
      (libsource (lib "Altium Content Vault") (part "PM-DCDC-LM2830XMF"))
    )
    (comp (ref "U201")
      (value "VIA LABS - VL805")
      (footprint "QFN40P800X800X90_HS-69N")
      (description "VL805 4-Port USB 3.0 Host Controller")
      (fields (field (name "MANUFACTURER") "VIA LABS") (field (name "MANUFACTURER PART NUMBER") "VL805-Q6"))
      (libsource (lib "ShareLib") (part "VIA LABS - VL805"))
    )
    (comp (ref "U202")
      (value "DIODES INCORPORATED - AP2182A")
      (footprint "SON65P300X60_HS-9N")
      (description "Power Switch/Driver 1:2 P-Channel 1.5A U-DFN3030-8 (Type E)")
      (fields
        (field (name "MANUFACTURER PART NUMBER") "AP2182AFGEG-7")
        (field (name "MANUFACTURER") "Diodes Incorporated")
      )
      (libsource (lib "ShareLib") (part "DIODES INCORPORATED - AP2182A"))
    )
    (comp (ref "U203")
      (value "DIODES INCORPORATED - AP2182A")
      (footprint "SON65P300X60_HS-9N")
      (description "Power Switch/Driver 1:2 P-Channel 1.5A U-DFN3030-8 (Type E)")
      (fields
        (field (name "MANUFACTURER PART NUMBER") "AP2182AFGEG-7")
        (field (name "MANUFACTURER") "Diodes Incorporated")
      )
      (libsource (lib "ShareLib") (part "DIODES INCORPORATED - AP2182A"))
    )
    (comp (ref "Y200")
      (value "ABRACON - ABM11-25.000MHZ-B7G-T")
      (footprint "ABM11")
      (description "25.000MHz ±15ppm Crystal 10pF 100 Ohm -20°C +70°C Surface Mount 4-SMD, No Lead (DFN, LCC)")
      (fields
        (field (name "MANUFACTURER") "ABRACON")
        (field (name "MANUFACTURER PART NUMBER") "ABM11-25.000MHZ-B7G-T")
      )
      (libsource (lib "ShareLib") (part "Crystal 4-Pin, 1+3-Feed / 2+4-GND"))
    )
  )
  (nets
    (net (code "1") (name "/DPR_SUPPORT_LTE") (class "Default")
      (node (ref "J202") (pin "27") (pintype "input"))
    )
    (net (code "2") (name "/EN1") (class "Default")
      (node (ref "R209") (pin "2") (pinfunction "2_2") (pintype "passive"))
      (node (ref "U201") (pin "44") (pinfunction "USBHPE1#_44") (pintype "output"))
      (node (ref "U202") (pin "4") (pinfunction "EN2_4") (pintype "input"))
    )
    (net (code "3") (name "/EN2") (class "Default")
      (node (ref "R211") (pin "2") (pinfunction "2_2") (pintype "passive"))
      (node (ref "U201") (pin "42") (pinfunction "USBHPE2#_42") (pintype "output"))
      (node (ref "U202") (pin "3") (pinfunction "EN1_3") (pintype "input"))
    )
    (net (code "4") (name "/EN3") (class "Default")
      (node (ref "R213") (pin "2") (pinfunction "2_2") (pintype "passive"))
      (node (ref "U201") (pin "40") (pinfunction "USBHPE3#_40") (pintype "output"))
      (node (ref "U203") (pin "4") (pinfunction "EN2_4") (pintype "input"))
    )
    (net (code "5") (name "/EN4") (class "Default")
      (node (ref "R215") (pin "2") (pinfunction "2_2") (pintype "passive"))
      (node (ref "U201") (pin "38") (pinfunction "USBHPE4#_38") (pintype "output"))
      (node (ref "U203") (pin "3") (pinfunction "EN1_3") (pintype "input"))
    )
    (net (code "6") (name "/FAN") (class "Default") (node (ref "J202") (pin "24") (pintype "input")))
    (net (code "7") (name "/FEEDBACK") (class "Default")
      (node (ref "R200") (pin "2") (pinfunction "2_2") (pintype "passive"))
      (node (ref "R202") (pin "2") (pinfunction "2_2") (pintype "passive"))
      (node (ref "U200") (pin "3") (pinfunction "FB_3") (pintype "input"))
    )
    (net (code "8") (name "/FULL_CARD_POWER_OFF_LTE") (class "Default")
      (node (ref "J202") (pin "33") (pintype "input"))
    )
    (net (code "9") (name "/GLOBAL_EN") (class "Default") (node (ref "J202") (pin "42") (pintype "input")))
    (net (code "10") (name "/I2C_SCL") (class "Default") (node (ref "J202") (pin "30") (pintype "input")))
    (net (code "11") (name "/I2C_SDA") (class "Default") (node (ref "J202") (pin "32") (pintype "input")))
    (net (code "12") (name "/MISO_CAN") (class "Default") (node (ref "J202") (pin "8") (pintype "input")))
    (net (code "13") (name "/MOSI_CAN") (class "Default") (node (ref "J202") (pin "4") (pintype "input")))
    (net (code "14") (name "/OC1") (class "Default")
      (node (ref "R210") (pin "2") (pinfunction "2_2") (pintype "passive"))
      (node (ref "U201") (pin "43") (pinfunction "USBHOC1#_43") (pintype "input"))
      (node (ref "U202") (pin "5") (pinfunction "FLG2_5") (pintype "output"))
    )
    (net (code "15") (name "/OC2") (class "Default")
      (node (ref "R212") (pin "2") (pinfunction "2_2") (pintype "passive"))
      (node (ref "U201") (pin "41") (pinfunction "USBHOC2#_41") (pintype "input"))
      (node (ref "U202") (pin "8") (pinfunction "FLG1_8") (pintype "output"))
    )
    (net (code "16") (name "/OC3") (class "Default")
      (node (ref "R214") (pin "2") (pinfunction "2_2") (pintype "passive"))
      (node (ref "U201") (pin "39") (pinfunction "USBHOC3#_39") (pintype "input"))
      (node (ref "U203") (pin "5") (pinfunction "FLG2_5") (pintype "output"))
    )
    (net (code "17") (name "/OC4") (class "Default")
      (node (ref "R216") (pin "2") (pinfunction "2_2") (pintype "passive"))
      (node (ref "U201") (pin "37") (pinfunction "USBHOC4#_37") (pintype "input"))
      (node (ref "U203") (pin "8") (pinfunction "FLG1_8") (pintype "output"))
    )
    (net (code "18") (name "/PCIe_CLK_N") (class "Default")
      (node (ref "U201") (pin "22") (pinfunction "PEXCLK-_22") (pintype "input"))
    )
    (net (code "19") (name "/PCIe_CLK_P") (class "Default")
      (node (ref "U201") (pin "21") (pinfunction "PEXCLK+_21") (pintype "input"))
    )
    (net (code "20") (name "/PCIe_CLK_nREQ") (class "Default")
      (node (ref "R205") (pin "2") (pinfunction "2_2") (pintype "passive"))
      (node (ref "U201") (pin "30") (pinfunction "PEXCREQ#_30") (pintype "output"))
    )
    (net (code "21") (name "/PCIe_RX_N") (class "Default")
      (node (ref "C228") (pin "2") (pinfunction "2_2") (pintype "passive"))
    )
    (net (code "22") (name "/PCIe_RX_P") (class "Default")
      (node (ref "C227") (pin "2") (pinfunction "2_2") (pintype "passive"))
    )
    (net (code "23") (name "/PCIe_TX_N") (class "Default")
      (node (ref "U201") (pin "28") (pinfunction "PEXRX-_28") (pintype "input"))
    )
    (net (code "24") (name "/PCIe_TX_P") (class "Default")
      (node (ref "U201") (pin "27") (pinfunction "PEXRX+_27") (pintype "input"))
    )
    (net (code "25") (name "/PCIe_nRST") (class "Default")
      (node (ref "C224") (pin "1") (pinfunction "1_1") (pintype "passive"))
      (node (ref "U201") (pin "19") (pinfunction "PEXRST#_19") (pintype "input"))
    )
    (net (code "26") (name "/PEXTX_N") (class "Default")
      (node (ref "C228") (pin "1") (pinfunction "1_1") (pintype "passive"))
      (node (ref "U201") (pin "25") (pinfunction "PEXTX-_25") (pintype "output"))
    )
    (net (code "27") (name "/PEXTX_P") (class "Default")
      (node (ref "C227") (pin "1") (pinfunction "1_1") (pintype "passive"))
      (node (ref "U201") (pin "24") (pinfunction "PEXTX+_24") (pintype "output"))
    )
    (net (code "28") (name "/PI-RX_STN-TX") (class "Default")
      (node (ref "J202") (pin "17") (pintype "input"))
    )
    (net (code "29") (name "/PI-TX_STN-RX") (class "Default")
      (node (ref "J202") (pin "15") (pintype "input"))
    )
    (net (code "30") (name "/PONRST") (class "Default")
      (node (ref "JP200") (pin "1") (pinfunction "1_1") (pintype "passive"))
      (node (ref "U201") (pin "31") (pinfunction "PONRST#_31") (pintype "input"))
    )
    (net (code "31") (name "/RESET_LTE_MODUL") (class "Default")
      (node (ref "J202") (pin "31") (pintype "input"))
    )
    (net (code "32") (name "/RESET_STN") (class "Default") (node (ref "J202") (pin "39") (pintype "input")))
    (net (code "33") (name "/RPI_RUNNING") (class "Default") (node (ref "J202") (pin "46") (pintype "input")))
    (net (code "34") (name "/SCK_CAN") (class "Default") (node (ref "J202") (pin "2") (pintype "input")))
    (net (code "35") (name "/SLEEP_STN") (class "Default") (node (ref "J202") (pin "37") (pintype "input")))
    (net (code "36") (name "/SSRX1_N") (class "Default")
      (node (ref "J200") (pin "14") (pinfunction "StdA_SSRX-_14") (pintype "output"))
      (node (ref "U201") (pin "56") (pinfunction "SSRX1-_56") (pintype "input"))
    )
    (net (code "37") (name "/SSRX1_P") (class "Default")
      (node (ref "J200") (pin "15") (pinfunction "StdA_SSRX+_15") (pintype "output"))
      (node (ref "U201") (pin "55") (pinfunction "SSRX1+_55") (pintype "input"))
    )
    (net (code "38") (name "/SSRX2_N") (class "Default")
      (node (ref "J200") (pin "5") (pinfunction "StdA_SSRX-_5") (pintype "output"))
      (node (ref "U201") (pin "65") (pinfunction "SSRX2-_65") (pintype "input"))
    )
    (net (code "39") (name "/SSRX2_P") (class "Default")
      (node (ref "J200") (pin "6") (pinfunction "StdA_SSRX+_6") (pintype "output"))
      (node (ref "U201") (pin "64") (pinfunction "SSRX2+_64") (pintype "input"))
    )
    (net (code "40") (name "/SSTX1_HUB_N") (class "Default")
      (node (ref "C223") (pin "2") (pinfunction "2_2") (pintype "passive"))
      (node (ref "U201") (pin "53") (pinfunction "SSTX1-_53") (pintype "output"))
    )
    (net (code "41") (name "/SSTX1_HUB_P") (class "Default")
      (node (ref "C222") (pin "2") (pinfunction "2_2") (pintype "passive"))
      (node (ref "U201") (pin "52") (pinfunction "SSTX1+_52") (pintype "output"))
    )
    (net (code "42") (name "/SSTX1_N") (class "Default")
      (node (ref "C223") (pin "1") (pinfunction "1_1") (pintype "passive"))
      (node (ref "J200") (pin "17") (pinfunction "StdA_SSTX-_17") (pintype "input"))
    )
    (net (code "43") (name "/SSTX1_P") (class "Default")
      (node (ref "C222") (pin "1") (pinfunction "1_1") (pintype "passive"))
      (node (ref "J200") (pin "18") (pinfunction "StdA_SSTX+_18") (pintype "input"))
    )
    (net (code "44") (name "/SSTX2_HUB_N") (class "Default")
      (node (ref "C226") (pin "2") (pinfunction "2_2") (pintype "passive"))
      (node (ref "U201") (pin "62") (pinfunction "SSTX2-_62") (pintype "output"))
    )
    (net (code "45") (name "/SSTX2_HUB_P") (class "Default")
      (node (ref "C225") (pin "2") (pinfunction "2_2") (pintype "passive"))
      (node (ref "U201") (pin "61") (pinfunction "SSTX2+_61") (pintype "output"))
    )
    (net (code "46") (name "/SSTX2_N") (class "Default")
      (node (ref "C226") (pin "1") (pinfunction "1_1") (pintype "passive"))
      (node (ref "J200") (pin "8") (pinfunction "StdA_SSTX-_8") (pintype "input"))
    )
    (net (code "47") (name "/SSTX2_P") (class "Default")
      (node (ref "C225") (pin "1") (pinfunction "1_1") (pintype "passive"))
      (node (ref "J200") (pin "9") (pinfunction "StdA_SSTX+_9") (pintype "input"))
    )
    (net (code "48") (name "/SSXI") (class "Default")
      (node (ref "R208") (pin "1") (pinfunction "1_1") (pintype "passive"))
      (node (ref "U201") (pin "47") (pinfunction "SSXI_47") (pintype "input"))
    )
    (net (code "49") (name "/SSXO") (class "Default")
      (node (ref "C229") (pin "2") (pinfunction "2_2") (pintype "passive"))
      (node (ref "U201") (pin "48") (pinfunction "SSXO_48") (pintype "output"))
      (node (ref "Y200") (pin "1") (pinfunction "1_1") (pintype "passive"))
    )
    (net (code "50") (name "/STN_RUNNING") (class "Default") (node (ref "J202") (pin "50") (pintype "input")))
    (net (code "51") (name "/SW") (class "Default")
      (node (ref "D200") (pin "1") (pinfunction "C_1") (pintype "passive"))
      (node (ref "L200") (pin "1") (pinfunction "1_1") (pintype "passive"))
      (node (ref "U200") (pin "1") (pinfunction "SW_1") (pintype "power_in"))
    )
    (net (code "52") (name "/TURN_OFF_GNSS") (class "Default")
      (node (ref "J202") (pin "21") (pintype "input"))
    )
    (net (code "53") (name "/TURN_OFF_WWAN") (class "Default")
      (node (ref "J202") (pin "25") (pintype "input"))
    )
    (net (code "54") (name "/USB2D1_N") (class "Default")
      (node (ref "J200") (pin "11") (pinfunction "D-_11") (pintype "bidirectional"))
      (node (ref "U201") (pin "59") (pinfunction "USB2D1-_59") (pintype "bidirectional"))
    )
    (net (code "55") (name "/USB2D1_P") (class "Default")
      (node (ref "J200") (pin "12") (pinfunction "D+_12") (pintype "bidirectional"))
      (node (ref "U201") (pin "58") (pinfunction "USB2D1+_58") (pintype "bidirectional"))
    )
    (net (code "56") (name "/USB2D2_N") (class "Default")
      (node (ref "J200") (pin "2") (pinfunction "D-_2") (pintype "bidirectional"))
      (node (ref "U201") (pin "68") (pinfunction "USB2D2-_68") (pintype "bidirectional"))
    )
    (net (code "57") (name "/USB2D2_P") (class "Default")
      (node (ref "J200") (pin "3") (pinfunction "D+_3") (pintype "bidirectional"))
      (node (ref "U201") (pin "67") (pinfunction "USB2D2+_67") (pintype "bidirectional"))
    )
    (net (code "58") (name "/USB2D3_N") (class "Default")
      (node (ref "J201") (pin "2") (pinfunction "D-_2") (pintype "bidirectional"))
      (node (ref "U201") (pin "8") (pinfunction "USB2D3-_8") (pintype "bidirectional"))
    )
    (net (code "59") (name "/USB2D3_P") (class "Default")
      (node (ref "J201") (pin "3") (pinfunction "D+_3") (pintype "bidirectional"))
      (node (ref "U201") (pin "7") (pinfunction "USB2D3+_7") (pintype "bidirectional"))
    )
    (net (code "60") (name "/USB2D4_N") (class "Default")
      (node (ref "J201") (pin "6") (pinfunction "D-_6") (pintype "bidirectional"))
      (node (ref "U201") (pin "17") (pinfunction "USB2D4-_17") (pintype "bidirectional"))
    )
    (net (code "61") (name "/USB2D4_P") (class "Default")
      (node (ref "J201") (pin "7") (pinfunction "D+_7") (pintype "bidirectional"))
      (node (ref "U201") (pin "16") (pinfunction "USB2D4+_16") (pintype "bidirectional"))
    )
    (net (code "62") (name "/USB_OTG") (class "Default") (node (ref "J202") (pin "1") (pintype "input")))
    (net (code "63") (name "/USB_UP_N") (class "Default") (node (ref "J202") (pin "7") (pintype "input")))
    (net (code "64") (name "/USB_UP_P") (class "Default") (node (ref "J202") (pin "5") (pintype "input")))
    (net (code "65") (name "/VBUS1") (class "Default")
      (node (ref "J200") (pin "10") (pinfunction "VBUS_10") (pintype "power_in"))
      (node (ref "U202") (pin "6") (pinfunction "OUT2_6") (pintype "power_in"))
    )
    (net (code "66") (name "/VBUS2") (class "Default")
      (node (ref "J200") (pin "1") (pinfunction "VBUS_1") (pintype "power_in"))
      (node (ref "U202") (pin "7") (pinfunction "OUT1_7") (pintype "power_in"))
    )
    (net (code "67") (name "/VBUS3") (class "Default")
      (node (ref "J201") (pin "1") (pinfunction "VBUS_1") (pintype "power_in"))
      (node (ref "U203") (pin "6") (pinfunction "OUT2_6") (pintype "power_in"))
    )
    (net (code "68") (name "/VBUS4") (class "Default")
      (node (ref "J201") (pin "5") (pinfunction "VBUS_5") (pintype "power_in"))
      (node (ref "U203") (pin "7") (pinfunction "OUT1_7") (pintype "power_in"))
    )
    (net (code "69") (name "/nCS1_CAN") (class "Default") (node (ref "J202") (pin "12") (pintype "input")))
    (net (code "70") (name "/nCS2_CAN") (class "Default") (node (ref "J202") (pin "22") (pintype "input")))
    (net (code "71") (name "/nINT1_CAN") (class "Default") (node (ref "J202") (pin "16") (pintype "input")))
    (net (code "72") (name "/nINT2_CAN") (class "Default") (node (ref "J202") (pin "20") (pintype "input")))
    (net (code "73") (name "/nRES_USB") (class "Default")
      (node (ref "JP200") (pin "2") (pinfunction "2_2") (pintype "passive"))
    )
    (net (code "74") (name "1V05") (class "Default")
      (node (ref "C211") (pin "1") (pinfunction "1_1") (pintype "passive"))
      (node (ref "C212") (pin "1") (pinfunction "1_1") (pintype "passive"))
      (node (ref "C213") (pin "1") (pinfunction "1_1") (pintype "passive"))
      (node (ref "C214") (pin "1") (pinfunction "1_1") (pintype "passive"))
      (node (ref "C215") (pin "1") (pinfunction "1_1") (pintype "passive"))
      (node (ref "C216") (pin "1") (pinfunction "1_1") (pintype "passive"))
      (node (ref "C217") (pin "1") (pinfunction "1_1") (pintype "passive"))
      (node (ref "C218") (pin "1") (pinfunction "1_1") (pintype "passive"))
      (node (ref "C219") (pin "1") (pinfunction "1_1") (pintype "passive"))
      (node (ref "C220") (pin "1") (pinfunction "1_1") (pintype "passive"))
      (node (ref "C221") (pin "1") (pinfunction "1_1") (pintype "passive"))
      (node (ref "C233") (pin "1") (pinfunction "1_1") (pintype "passive"))
      (node (ref "C237") (pin "1") (pinfunction "1_1") (pintype "passive"))
      (node (ref "L200") (pin "2") (pinfunction "2_2") (pintype "passive"))
      (node (ref "R200") (pin "1") (pinfunction "1_1") (pintype "passive"))
      (node (ref "U201") (pin "12") (pinfunction "VCCA10SSRX34_12") (pintype "power_in"))
      (node (ref "U201") (pin "29") (pinfunction "VDD_29") (pintype "power_in"))
      (node (ref "U201") (pin "3") (pinfunction "VCCA10SSRX34_3") (pintype "power_in"))
      (node (ref "U201") (pin "45") (pinfunction "VDD_45") (pintype "power_in"))
      (node (ref "U201") (pin "54") (pinfunction "VCCA10SSRX12_54") (pintype "power_in"))
      (node (ref "U201") (pin "60") (pinfunction "VDD_60") (pintype "power_in"))
      (node (ref "U201") (pin "63") (pinfunction "VCCA10SSRX12_63") (pintype "power_in"))
      (node (ref "U201") (pin "9") (pinfunction "VDD_9") (pintype "power_in"))
    )
    (net (code "75") (name "3V3") (class "Default")
      (node (ref "C200") (pin "1") (pinfunction "1_1") (pintype "passive"))
      (node (ref "C201") (pin "1") (pinfunction "1_1") (pintype "passive"))
      (node (ref "C202") (pin "1") (pinfunction "1_1") (pintype "passive"))
      (node (ref "C203") (pin "1") (pinfunction "1_1") (pintype "passive"))
      (node (ref "C204") (pin "1") (pinfunction "1_1") (pintype "passive"))
      (node (ref "C205") (pin "1") (pinfunction "1_1") (pintype "passive"))
      (node (ref "C206") (pin "1") (pinfunction "1_1") (pintype "passive"))
      (node (ref "C207") (pin "1") (pinfunction "1_1") (pintype "passive"))
      (node (ref "C208") (pin "1") (pinfunction "1_1") (pintype "passive"))
      (node (ref "D201") (pin "1") (pinfunction "C_1") (pintype "passive"))
      (node (ref "J202") (pin "41") (pintype "input"))
      (node (ref "J202") (pin "43") (pintype "input"))
      (node (ref "R203") (pin "2") (pinfunction "2_2") (pintype "passive"))
      (node (ref "R204") (pin "1") (pinfunction "1_1") (pintype "passive"))
      (node (ref "R205") (pin "1") (pinfunction "1_1") (pintype "passive"))
      (node (ref "R207") (pin "1") (pinfunction "1_1") (pintype "passive"))
      (node (ref "R209") (pin "1") (pinfunction "1_1") (pintype "passive"))
      (node (ref "R210") (pin "1") (pinfunction "1_1") (pintype "passive"))
      (node (ref "R211") (pin "1") (pinfunction "1_1") (pintype "passive"))
      (node (ref "R212") (pin "1") (pinfunction "1_1") (pintype "passive"))
      (node (ref "R213") (pin "1") (pinfunction "1_1") (pintype "passive"))
      (node (ref "R214") (pin "1") (pinfunction "1_1") (pintype "passive"))
      (node (ref "R215") (pin "1") (pinfunction "1_1") (pintype "passive"))
      (node (ref "R216") (pin "1") (pinfunction "1_1") (pintype "passive"))
      (node (ref "U201") (pin "15") (pinfunction "VCCA33SS34_15") (pintype "power_in"))
      (node (ref "U201") (pin "23") (pinfunction "VCCA33PEX_23") (pintype "power_in"))
      (node (ref "U201") (pin "32") (pinfunction "VSUS33_32") (pintype "power_in"))
      (node (ref "U201") (pin "46") (pinfunction "VSUS33_46") (pintype "power_in"))
      (node (ref "U201") (pin "49") (pinfunction "VCCA33SSM_49") (pintype "power_in"))
      (node (ref "U201") (pin "57") (pinfunction "VCCA33SS12_57") (pintype "power_in"))
      (node (ref "U201") (pin "6") (pinfunction "VCCA33SS34_6") (pintype "power_in"))
      (node (ref "U201") (pin "66") (pinfunction "VCCA33SS12_66") (pintype "power_in"))
    )
    (net (code "76") (name "3V3_PO") (class "Default") (node (ref "J202") (pin "28") (pintype "input")))
    (net (code "77") (name "5V") (class "Default")
      (node (ref "C209") (pin "1") (pinfunction "1_1") (pintype "passive"))
      (node (ref "C210") (pin "1") (pinfunction "1_1") (pintype "passive"))
      (node (ref "C231") (pin "1") (pinfunction "1_1") (pintype "passive"))
      (node (ref "C232") (pin "1") (pinfunction "1_1") (pintype "passive"))
      (node (ref "C234") (pin "2") (pinfunction "2_2") (pintype "passive"))
      (node (ref "C235") (pin "1") (pinfunction "1_1") (pintype "passive"))
      (node (ref "C236") (pin "1") (pinfunction "1_1") (pintype "passive"))
      (node (ref "C239") (pin "1") (pinfunction "1_1") (pintype "passive"))
      (node (ref "C240") (pin "1") (pinfunction "1_1") (pintype "passive"))
      (node (ref "J202") (pin "11") (pintype "input"))
      (node (ref "J202") (pin "47") (pintype "input"))
      (node (ref "J202") (pin "49") (pintype "input"))
      (node (ref "J202") (pin "9") (pintype "input"))
      (node (ref "R201") (pin "2") (pinfunction "2_2") (pintype "passive"))
      (node (ref "U200") (pin "5") (pinfunction "VIN_5") (pintype "power_in"))
      (node (ref "U202") (pin "2") (pinfunction "IN_2") (pintype "power_in"))
      (node (ref "U203") (pin "2") (pinfunction "IN_2") (pintype "power_in"))
    )
    (net (code "78") (name "5V_PO") (class "Default")
      (node (ref "J202") (pin "36") (pintype "input"))
      (node (ref "J202") (pin "38") (pintype "input"))
    )
    (net (code "79") (name "GND") (class "Default")
      (node (ref "C200") (pin "2") (pinfunction "2_2") (pintype "passive"))
      (node (ref "C201") (pin "2") (pinfunction "2_2") (pintype "passive"))
      (node (ref "C202") (pin "2") (pinfunction "2_2") (pintype "passive"))
      (node (ref "C203") (pin "2") (pinfunction "2_2") (pintype "passive"))
      (node (ref "C204") (pin "2") (pinfunction "2_2") (pintype "passive"))
      (node (ref "C205") (pin "2") (pinfunction "2_2") (pintype "passive"))
      (node (ref "C206") (pin "2") (pinfunction "2_2") (pintype "passive"))
      (node (ref "C207") (pin "2") (pinfunction "2_2") (pintype "passive"))
      (node (ref "C208") (pin "2") (pinfunction "2_2") (pintype "passive"))
      (node (ref "C209") (pin "2") (pinfunction "2_2") (pintype "passive"))
      (node (ref "C210") (pin "2") (pinfunction "2_2") (pintype "passive"))
      (node (ref "C211") (pin "2") (pinfunction "2_2") (pintype "passive"))
      (node (ref "C212") (pin "2") (pinfunction "2_2") (pintype "passive"))
      (node (ref "C213") (pin "2") (pinfunction "2_2") (pintype "passive"))
      (node (ref "C214") (pin "2") (pinfunction "2_2") (pintype "passive"))
      (node (ref "C215") (pin "2") (pinfunction "2_2") (pintype "passive"))
      (node (ref "C216") (pin "2") (pinfunction "2_2") (pintype "passive"))
      (node (ref "C217") (pin "2") (pinfunction "2_2") (pintype "passive"))
      (node (ref "C218") (pin "2") (pinfunction "2_2") (pintype "passive"))
      (node (ref "C219") (pin "2") (pinfunction "2_2") (pintype "passive"))
      (node (ref "C220") (pin "2") (pinfunction "2_2") (pintype "passive"))
      (node (ref "C221") (pin "2") (pinfunction "2_2") (pintype "passive"))
      (node (ref "C224") (pin "2") (pinfunction "2_2") (pintype "passive"))
      (node (ref "C229") (pin "1") (pinfunction "1_1") (pintype "passive"))
      (node (ref "C230") (pin "1") (pinfunction "1_1") (pintype "passive"))
      (node (ref "C231") (pin "2") (pinfunction "2_2") (pintype "passive"))
      (node (ref "C232") (pin "2") (pinfunction "2_2") (pintype "passive"))
      (node (ref "C233") (pin "2") (pinfunction "2_2") (pintype "passive"))
      (node (ref "C234") (pin "1") (pinfunction "1_1") (pintype "passive"))
      (node (ref "C235") (pin "2") (pinfunction "2_2") (pintype "passive"))
      (node (ref "C236") (pin "2") (pinfunction "2_2") (pintype "passive"))
      (node (ref "C237") (pin "2") (pinfunction "2_2") (pintype "passive"))
      (node (ref "C238") (pin "2") (pinfunction "2_2") (pintype "passive"))
      (node (ref "C239") (pin "2") (pinfunction "2_2") (pintype "passive"))
      (node (ref "C240") (pin "2") (pinfunction "2_2") (pintype "passive"))
      (node (ref "D200") (pin "2") (pinfunction "A_2") (pintype "passive"))
      (node (ref "J200") (pin "13") (pinfunction "GND_13") (pintype "power_in"))
      (node (ref "J200") (pin "16") (pinfunction "GND_DRAIN_16") (pintype "power_in"))
      (node (ref "J200") (pin "19") (pinfunction "Shield_19") (pintype "passive"))
      (node (ref "J200") (pin "4") (pinfunction "GND_4") (pintype "power_in"))
      (node (ref "J200") (pin "7") (pinfunction "GND_DRAIN_7") (pintype "power_in"))
      (node (ref "J201") (pin "4") (pinfunction "GND_4") (pintype "power_in"))
      (node (ref "J201") (pin "8") (pinfunction "GND_8") (pintype "power_in"))
      (node (ref "J201") (pin "9") (pinfunction "Shield_9") (pintype "passive"))
      (node (ref "J202") (pin "10") (pintype "input"))
      (node (ref "J202") (pin "13") (pintype "input"))
      (node (ref "J202") (pin "14") (pintype "input"))
      (node (ref "J202") (pin "18") (pintype "input"))
      (node (ref "J202") (pin "19") (pintype "input"))
      (node (ref "J202") (pin "23") (pintype "input"))
      (node (ref "J202") (pin "26") (pintype "input"))
      (node (ref "J202") (pin "29") (pintype "input"))
      (node (ref "J202") (pin "3") (pintype "input"))
      (node (ref "J202") (pin "34") (pintype "input"))
      (node (ref "J202") (pin "35") (pintype "input"))
      (node (ref "J202") (pin "40") (pintype "input"))
      (node (ref "J202") (pin "44") (pintype "input"))
      (node (ref "J202") (pin "45") (pintype "input"))
      (node (ref "J202") (pin "48") (pintype "input"))
      (node (ref "J202") (pin "6") (pintype "input"))
      (node (ref "R202") (pin "1") (pinfunction "1_1") (pintype "passive"))
      (node (ref "R206") (pin "1") (pinfunction "1_1") (pintype "passive"))
      (node (ref "U200") (pin "2") (pinfunction "GND_2") (pintype "power_in"))
      (node (ref "U201") (pin "69") (pinfunction "EP_69") (pintype "power_in"))
      (node (ref "U202") (pin "1") (pinfunction "GND_1") (pintype "power_in"))
      (node (ref "U202") (pin "9") (pinfunction "ePad_9") (pintype "power_in"))
      (node (ref "U203") (pin "1") (pinfunction "GND_1") (pintype "power_in"))
      (node (ref "U203") (pin "9") (pinfunction "ePad_9") (pintype "power_in"))
      (node (ref "Y200") (pin "2") (pinfunction "GND_2") (pintype "power_in"))
      (node (ref "Y200") (pin "4") (pinfunction "GND_4") (pintype "power_in"))
    )
    (net (code "80") (name "Net-(C230-Pad2)") (class "Default")
      (node (ref "C230") (pin "2") (pinfunction "2_2") (pintype "passive"))
      (node (ref "R208") (pin "2") (pinfunction "2_2") (pintype "passive"))
      (node (ref "Y200") (pin "3") (pinfunction "3_3") (pintype "passive"))
    )
    (net (code "81") (name "Net-(D201-A)") (class "Default")
      (node (ref "C238") (pin "1") (pinfunction "1_1") (pintype "passive"))
      (node (ref "D201") (pin "2") (pinfunction "A_2") (pintype "passive"))
      (node (ref "JP200") (pin "3") (pinfunction "3_3") (pintype "passive"))
      (node (ref "R203") (pin "1") (pinfunction "1_1") (pintype "passive"))
    )
    (net (code "82") (name "Net-(U200-EN)") (class "Default")
      (node (ref "R201") (pin "1") (pinfunction "1_1") (pintype "passive"))
      (node (ref "U200") (pin "4") (pinfunction "EN_4") (pintype "input"))
    )
    (net (code "83") (name "Net-(U201-PEXWAKE#)") (class "Default")
      (node (ref "R204") (pin "2") (pinfunction "2_2") (pintype "passive"))
      (node (ref "U201") (pin "20") (pinfunction "PEXWAKE#_20") (pintype "output"))
    )
    (net (code "84") (name "Net-(U201-SMI#)") (class "Default")
      (node (ref "R207") (pin "2") (pinfunction "2_2") (pintype "passive"))
      (node (ref "U201") (pin "18") (pinfunction "SMI#_18") (pintype "output"))
    )
    (net (code "85") (name "Net-(U201-SSREXT)") (class "Default")
      (node (ref "R206") (pin "2") (pinfunction "2_2") (pintype "passive"))
      (node (ref "U201") (pin "50") (pinfunction "SSREXT_50") (pintype "passive"))
    )
    (net (code "86") (name "unconnected-(U201-NC-Pad26)") (class "Default")
      (node (ref "U201") (pin "26") (pinfunction "NC_26") (pintype "passive"))
    )
    (net (code "87") (name "unconnected-(U201-SPICK-Pad35)") (class "Default")
      (node (ref "U201") (pin "35") (pinfunction "SPICK_35") (pintype "output+no_connect"))
    )
    (net (code "88") (name "unconnected-(U201-SPICS#-Pad34)") (class "Default")
      (node (ref "U201") (pin "34") (pinfunction "SPICS#_34") (pintype "output+no_connect"))
    )
    (net (code "89") (name "unconnected-(U201-SPISI-Pad36)") (class "Default")
      (node (ref "U201") (pin "36") (pinfunction "SPISI_36") (pintype "output+no_connect"))
    )
    (net (code "90") (name "unconnected-(U201-SPISO-Pad33)") (class "Default")
      (node (ref "U201") (pin "33") (pinfunction "SPISO_33") (pintype "input+no_connect"))
    )
    (net (code "91") (name "unconnected-(U201-SSRX3+-Pad4)") (class "Default")
      (node (ref "U201") (pin "4") (pinfunction "SSRX3+_4") (pintype "input+no_connect"))
    )
    (net (code "92") (name "unconnected-(U201-SSRX3--Pad5)") (class "Default")
      (node (ref "U201") (pin "5") (pinfunction "SSRX3-_5") (pintype "input+no_connect"))
    )
    (net (code "93") (name "unconnected-(U201-SSRX4+-Pad13)") (class "Default")
      (node (ref "U201") (pin "13") (pinfunction "SSRX4+_13") (pintype "input+no_connect"))
    )
    (net (code "94") (name "unconnected-(U201-SSRX4--Pad14)") (class "Default")
      (node (ref "U201") (pin "14") (pinfunction "SSRX4-_14") (pintype "input+no_connect"))
    )
    (net (code "95") (name "unconnected-(U201-SSTX3+-Pad1)") (class "Default")
      (node (ref "U201") (pin "1") (pinfunction "SSTX3+_1") (pintype "output+no_connect"))
    )
    (net (code "96") (name "unconnected-(U201-SSTX3--Pad2)") (class "Default")
      (node (ref "U201") (pin "2") (pinfunction "SSTX3-_2") (pintype "output+no_connect"))
    )
    (net (code "97") (name "unconnected-(U201-SSTX4+-Pad10)") (class "Default")
      (node (ref "U201") (pin "10") (pinfunction "SSTX4+_10") (pintype "output+no_connect"))
    )
    (net (code "98") (name "unconnected-(U201-SSTX4--Pad11)") (class "Default")
      (node (ref "U201") (pin "11") (pinfunction "SSTX4-_11") (pintype "output+no_connect"))
    )
    (net (code "99") (name "unconnected-(U201-TESTEN-Pad51)") (class "Default")
      (node (ref "U201") (pin "51") (pinfunction "TESTEN_51") (pintype "input+no_connect"))
    )
  )
)
